# R2P_PS_module.net
KiCad netlist of a schematic drawn in EAGLE
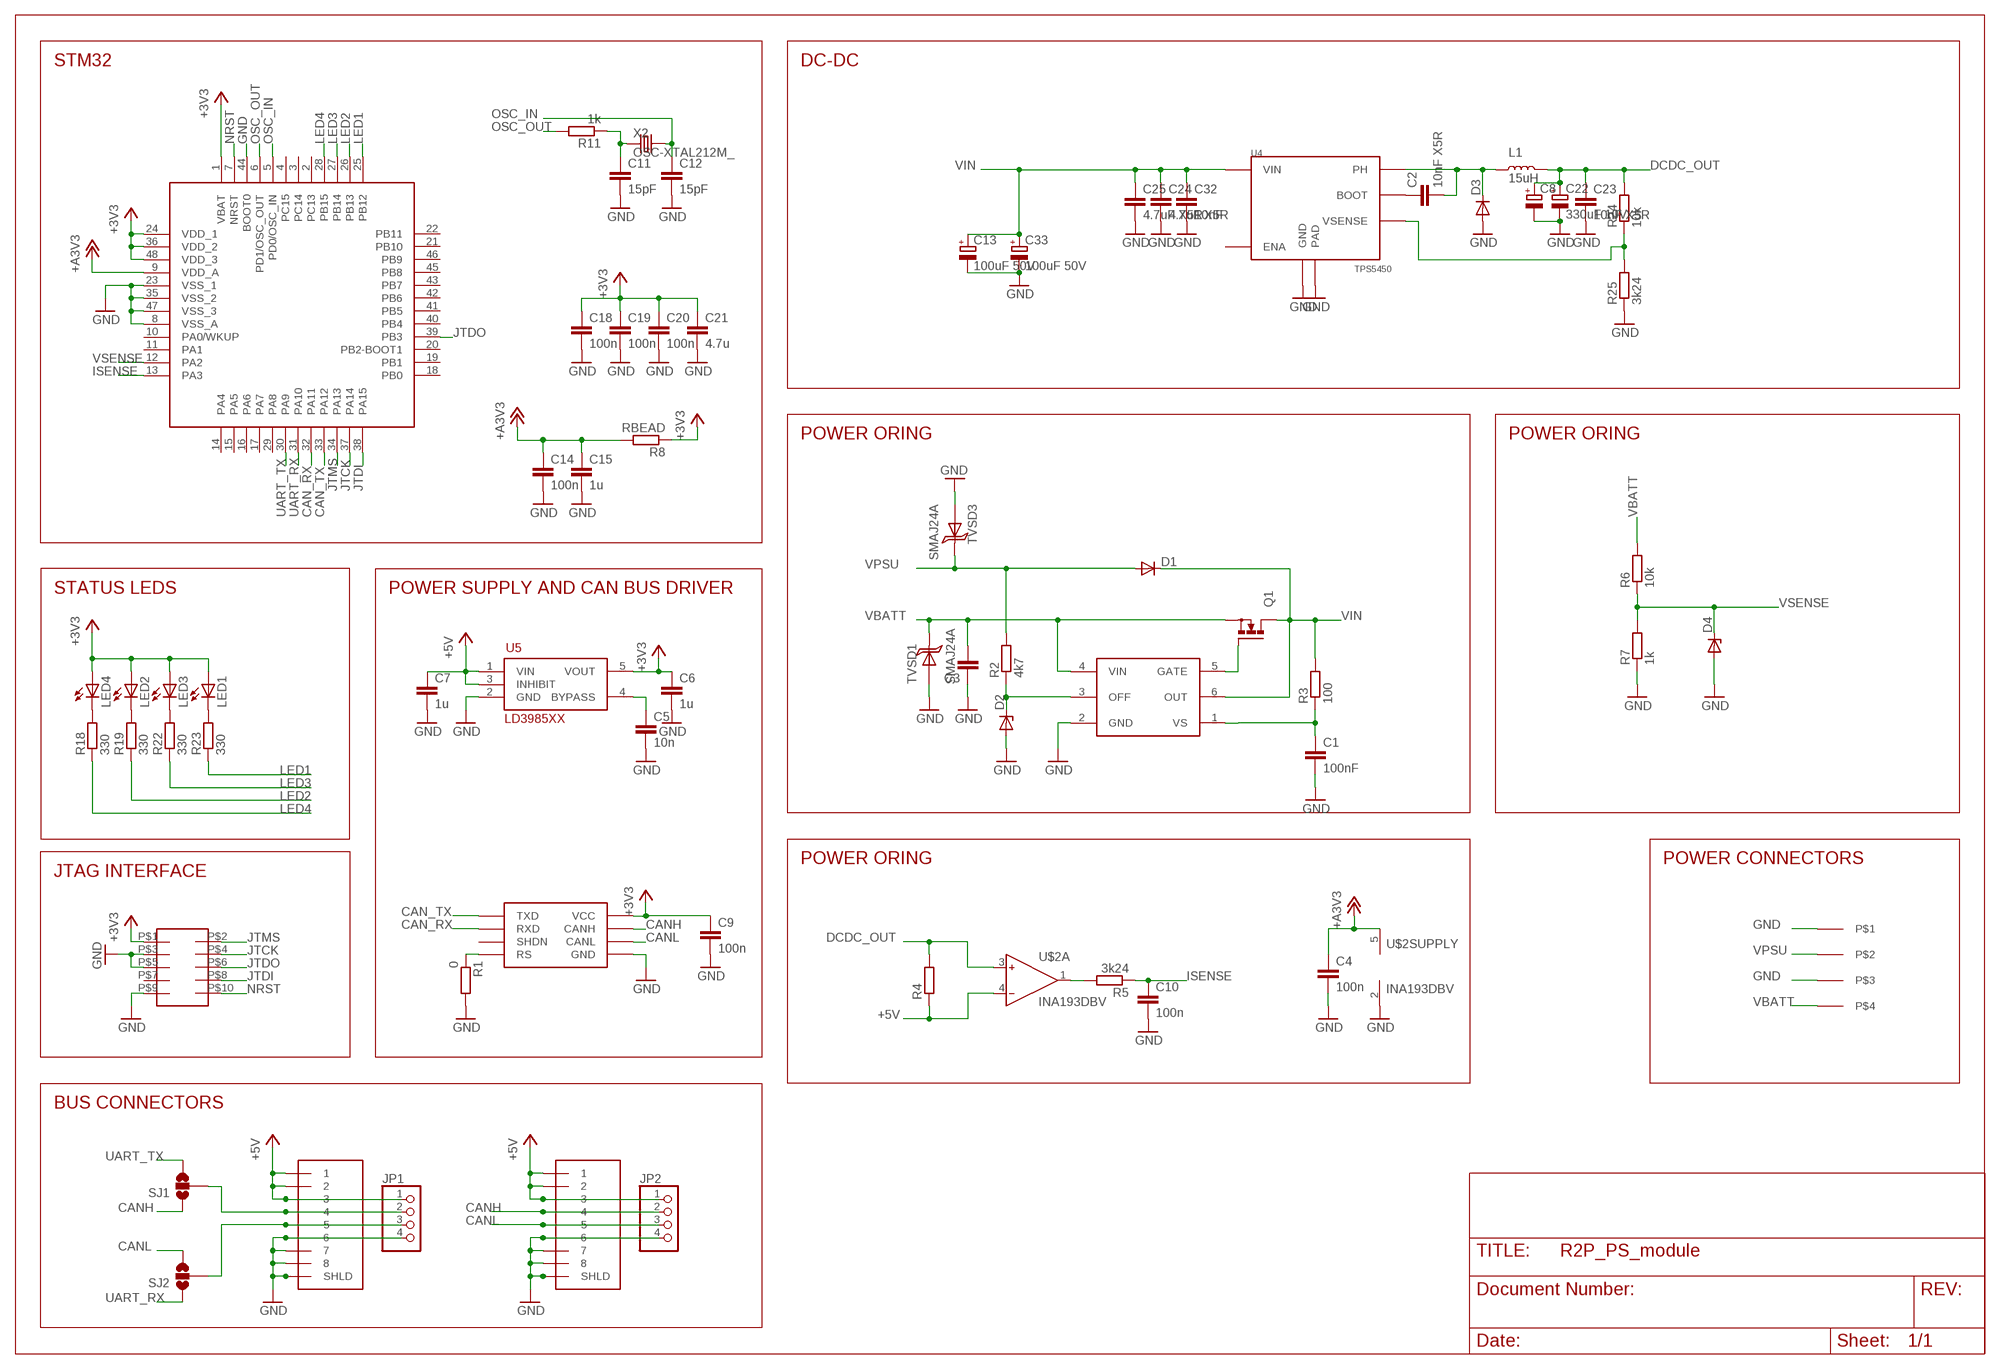
[diagram p0: schematic, sheet 1]

(export (version "E")
  (design (tool "Eeschema 10.0.6"))
  (components
    (comp (ref "1")
      (value "RJ45-43860")
      (footprint "eagle-import:0438600010")
      (libsource (lib "eagle-import") (part "RJ45-43860"))
    )
    (comp (ref "2")
      (value "RJ45-43860")
      (footprint "eagle-import:0438600010")
      (libsource (lib "eagle-import") (part "RJ45-43860"))
    )
    (comp (ref "C1")
      (value "100nF")
      (footprint "eagle-import:C0603")
      (libsource (lib "eagle-import") (part "C-EUC0603"))
    )
    (comp (ref "C2")
      (value "10nF X5R")
      (footprint "eagle-import:C0603")
      (libsource (lib "eagle-import") (part "C-EUC0603"))
    )
    (comp (ref "C3")
      (value "C-EUC0805")
      (footprint "eagle-import:C0805")
      (libsource (lib "eagle-import") (part "C-EUC0805"))
    )
    (comp (ref "C4")
      (value "100n")
      (footprint "eagle-import:C0603")
      (libsource (lib "eagle-import") (part "C-EUC0603"))
    )
    (comp (ref "C5")
      (value "10n")
      (footprint "eagle-import:C0603")
      (libsource (lib "eagle-import") (part "C-EUC0603"))
    )
    (comp (ref "C6")
      (value "1u")
      (footprint "eagle-import:C0603")
      (libsource (lib "eagle-import") (part "C-EUC0603"))
    )
    (comp (ref "C7")
      (value "1u")
      (footprint "eagle-import:C0603")
      (libsource (lib "eagle-import") (part "C-EUC0603"))
    )
    (comp (ref "C8")
      (value "CPOL-EUE5-10.5")
      (footprint "eagle-import:E5-10,5")
      (libsource (lib "eagle-import") (part "CPOL-EUE5-10.5"))
    )
    (comp (ref "C9")
      (value "100n")
      (footprint "eagle-import:C0603")
      (libsource (lib "eagle-import") (part "C-EUC0603"))
    )
    (comp (ref "C10")
      (value "100n")
      (footprint "eagle-import:C0603")
      (libsource (lib "eagle-import") (part "C-EUC0603"))
    )
    (comp (ref "C11")
      (value "15pF")
      (footprint "eagle-import:C0603")
      (libsource (lib "eagle-import") (part "C-EUC0603"))
    )
    (comp (ref "C12")
      (value "15pF")
      (footprint "eagle-import:C0603")
      (libsource (lib "eagle-import") (part "C-EUC0603"))
    )
    (comp (ref "C13")
      (value "100uF 50V")
      (footprint "eagle-import:E5-10,5")
      (libsource (lib "eagle-import") (part "CPOL-EUE5-10.5"))
    )
    (comp (ref "C14")
      (value "100n")
      (footprint "eagle-import:C0603")
      (libsource (lib "eagle-import") (part "C-EUC0603"))
    )
    (comp (ref "C15")
      (value "1u")
      (footprint "eagle-import:C0603")
      (libsource (lib "eagle-import") (part "C-EUC0603"))
    )
    (comp (ref "C18")
      (value "100n")
      (footprint "eagle-import:C0603")
      (libsource (lib "eagle-import") (part "C-EUC0603"))
    )
    (comp (ref "C19")
      (value "100n")
      (footprint "eagle-import:C0603")
      (libsource (lib "eagle-import") (part "C-EUC0603"))
    )
    (comp (ref "C20")
      (value "100n")
      (footprint "eagle-import:C0603")
      (libsource (lib "eagle-import") (part "C-EUC0603"))
    )
    (comp (ref "C21")
      (value "4.7u")
      (footprint "eagle-import:C0805")
      (libsource (lib "eagle-import") (part "C-EUC0805"))
    )
    (comp (ref "C22")
      (value "330uF 10V")
      (footprint "eagle-import:E2,5-7")
      (libsource (lib "eagle-import") (part "CPOL-EUE2.5-7"))
    )
    (comp (ref "C23")
      (value "10nF X5R")
      (footprint "eagle-import:C0603")
      (libsource (lib "eagle-import") (part "C-EUC0603"))
    )
    (comp (ref "C24")
      (value "4.7uF X5R")
      (footprint "eagle-import:C1210")
      (libsource (lib "eagle-import") (part "C-EUC1210"))
    )
    (comp (ref "C25")
      (value "4.7uF X5R")
      (footprint "eagle-import:C1210")
      (libsource (lib "eagle-import") (part "C-EUC1210"))
    )
    (comp (ref "C32")
      (value "10nF")
      (footprint "eagle-import:C0603")
      (libsource (lib "eagle-import") (part "C-EUC0603"))
    )
    (comp (ref "C33")
      (value "100uF 50V")
      (footprint "eagle-import:E2,5-7")
      (libsource (lib "eagle-import") (part "CPOL-EUE2.5-7"))
    )
    (comp (ref "D1")
      (value "DIODE-DO-214AC")
      (footprint "eagle-import:DO-214AC")
      (libsource (lib "eagle-import") (part "DIODE-DO-214AC"))
    )
    (comp (ref "D2")
      (value "ZENERSOD-323F")
      (footprint "eagle-import:SOD-323F")
      (libsource (lib "eagle-import") (part "ZENERSOD-323F"))
    )
    (comp (ref "D3")
      (value "DIODE-DO-214AC")
      (footprint "eagle-import:DO-214AC")
      (libsource (lib "eagle-import") (part "DIODE-DO-214AC"))
    )
    (comp (ref "D4")
      (value "ZENERSOD-323F")
      (footprint "eagle-import:SOD-323F")
      (libsource (lib "eagle-import") (part "ZENERSOD-323F"))
    )
    (comp (ref "JP1")
      (value "PINHD-1X4/90")
      (footprint "eagle-import:1X04_90")
      (libsource (lib "eagle-import") (part "PINHD-1X4/90"))
    )
    (comp (ref "JP2")
      (value "PINHD-1X4/90")
      (footprint "eagle-import:1X04_90")
      (libsource (lib "eagle-import") (part "PINHD-1X4/90"))
    )
    (comp (ref "L1")
      (value "15uH")
      (footprint "eagle-import:CDRH127")
      (libsource (lib "eagle-import") (part "CDRH127"))
    )
    (comp (ref "LED1")
      (value "LEDCHIPLED_0805")
      (footprint "eagle-import:CHIPLED_0805")
      (libsource (lib "eagle-import") (part "LEDCHIPLED_0805"))
    )
    (comp (ref "LED2")
      (value "LEDCHIPLED_0805")
      (footprint "eagle-import:CHIPLED_0805")
      (libsource (lib "eagle-import") (part "LEDCHIPLED_0805"))
    )
    (comp (ref "LED3")
      (value "LEDCHIPLED_0805")
      (footprint "eagle-import:CHIPLED_0805")
      (libsource (lib "eagle-import") (part "LEDCHIPLED_0805"))
    )
    (comp (ref "LED4")
      (value "LEDCHIPLED_0805")
      (footprint "eagle-import:CHIPLED_0805")
      (libsource (lib "eagle-import") (part "LEDCHIPLED_0805"))
    )
    (comp (ref "Q1")
      (value "N-MOSFET-SO8S")
      (footprint "eagle-import:SO-08")
      (libsource (lib "eagle-import") (part "N-MOSFET-SO8S"))
    )
    (comp (ref "R1")
      (value "0")
      (footprint "eagle-import:R0603")
      (libsource (lib "eagle-import") (part "R-EU_R0603"))
    )
    (comp (ref "R2")
      (value "4k7")
      (footprint "eagle-import:R0603")
      (libsource (lib "eagle-import") (part "R-EU_R0603"))
    )
    (comp (ref "R3")
      (value "100")
      (footprint "eagle-import:R0603")
      (libsource (lib "eagle-import") (part "R-EU_R0603"))
    )
    (comp (ref "R4")
      (value "R-EU_R2512")
      (footprint "eagle-import:R2512")
      (libsource (lib "eagle-import") (part "R-EU_R2512"))
    )
    (comp (ref "R5")
      (value "3k24")
      (footprint "eagle-import:R0603")
      (libsource (lib "eagle-import") (part "R-EU_R0603"))
    )
    (comp (ref "R6")
      (value "10k")
      (footprint "eagle-import:R0603")
      (libsource (lib "eagle-import") (part "R-EU_R0603"))
    )
    (comp (ref "R7")
      (value "1k")
      (footprint "eagle-import:R0603")
      (libsource (lib "eagle-import") (part "R-EU_R0603"))
    )
    (comp (ref "R8")
      (value "RBEAD")
      (footprint "eagle-import:R0603")
      (libsource (lib "eagle-import") (part "R-EU_R0603"))
    )
    (comp (ref "R11")
      (value "1k")
      (footprint "eagle-import:R0603")
      (libsource (lib "eagle-import") (part "R-EU_R0603"))
    )
    (comp (ref "R18")
      (value "330")
      (footprint "eagle-import:R0603")
      (libsource (lib "eagle-import") (part "R-EU_R0603"))
    )
    (comp (ref "R19")
      (value "330")
      (footprint "eagle-import:R0603")
      (libsource (lib "eagle-import") (part "R-EU_R0603"))
    )
    (comp (ref "R22")
      (value "330")
      (footprint "eagle-import:R0603")
      (libsource (lib "eagle-import") (part "R-EU_R0603"))
    )
    (comp (ref "R23")
      (value "330")
      (footprint "eagle-import:R0603")
      (libsource (lib "eagle-import") (part "R-EU_R0603"))
    )
    (comp (ref "R24")
      (value "10k")
      (footprint "eagle-import:R0603")
      (libsource (lib "eagle-import") (part "R-EU_R0603"))
    )
    (comp (ref "R25")
      (value "3k24")
      (footprint "eagle-import:R0603")
      (libsource (lib "eagle-import") (part "R-EU_R0603"))
    )
    (comp (ref "SJ1")
      (value "SOLDERJUMPER_2WAYPASTE1&2")
      (footprint "eagle-import:SJ_3_PASTE1&2")
      (libsource (lib "eagle-import") (part "SOLDERJUMPER_2WAYPASTE1&2"))
    )
    (comp (ref "SJ2")
      (value "SOLDERJUMPER_2WAYPASTE1&2")
      (footprint "eagle-import:SJ_3_PASTE1&2")
      (libsource (lib "eagle-import") (part "SOLDERJUMPER_2WAYPASTE1&2"))
    )
    (comp (ref "SOT1")
      (value "MAX3051")
      (footprint "eagle-import:SOT23-8L")
      (libsource (lib "eagle-import") (part "MAX3051"))
    )
    (comp (ref "TVSD1")
      (value "SMAJ24A")
      (footprint "eagle-import:SMA")
      (libsource (lib "eagle-import") (part "TVSDSMA"))
    )
    (comp (ref "TVSD3")
      (value "SMAJ24A")
      (footprint "eagle-import:SMA")
      (libsource (lib "eagle-import") (part "TVSDSMA"))
    )
    (comp (ref "U$1")
      (value "LM5050-1")
      (footprint "eagle-import:SOT23-6L")
      (libsource (lib "eagle-import") (part "LM5050-1"))
    )
    (comp (ref "U$2")
      (value "INA193DBV")
      (footprint "eagle-import:SOT23-5L")
      (libsource (lib "eagle-import") (part "INA193DBV"))
    )
    (comp (ref "U$3")
      (value "POWERCONN-4")
      (footprint "eagle-import:POWERCONN-4")
      (libsource (lib "eagle-import") (part "POWERCONN-4"))
    )
    (comp (ref "U$4")
      (value "FTSH-105")
      (footprint "eagle-import:FTSH-105")
      (libsource (lib "eagle-import") (part "FTSH-105"))
    )
    (comp (ref "U1")
      (value "STM32F103CX")
      (footprint "eagle-import:LQFP48")
      (libsource (lib "eagle-import") (part "STM32F103CX"))
    )
    (comp (ref "U4")
      (value "TPS5450")
      (footprint "eagle-import:POWERPAD-SO8")
      (libsource (lib "eagle-import") (part "TPS5450"))
    )
    (comp (ref "U5")
      (value "LD3985XX")
      (footprint "eagle-import:SOT23-5L")
      (libsource (lib "eagle-import") (part "LD3985XX"))
    )
    (comp (ref "X2")
      (value "OSC-XTAL212M_")
      (footprint "eagle-import:4X6")
      (libsource (lib "eagle-import") (part "OSC-XTAL212M_"))
    )
  )
  (nets
    (net (code "1") (name "+3V3") (class "Default")
      (node (ref "C18") (pin "1") (pinfunction "1_1") (pintype "passive"))
      (node (ref "C19") (pin "1") (pinfunction "1_1") (pintype "passive"))
      (node (ref "C20") (pin "1") (pinfunction "1_1") (pintype "passive"))
      (node (ref "C21") (pin "1") (pinfunction "1_1") (pintype "passive"))
      (node (ref "C6") (pin "1") (pinfunction "1_1") (pintype "passive"))
      (node (ref "C9") (pin "1") (pinfunction "1_1") (pintype "passive"))
      (node (ref "LED1") (pin "A") (pinfunction "A_A") (pintype "passive"))
      (node (ref "LED2") (pin "A") (pinfunction "A_A") (pintype "passive"))
      (node (ref "LED3") (pin "A") (pinfunction "A_A") (pintype "passive"))
      (node (ref "LED4") (pin "A") (pinfunction "A_A") (pintype "passive"))
      (node (ref "R8") (pin "1") (pinfunction "1_1") (pintype "passive"))
      (node (ref "SOT1") (pin "P$3") (pinfunction "VCC_P$3") (pintype "bidirectional"))
      (node (ref "U$4") (pin "P$1") (pinfunction "P$1_P$1") (pintype "bidirectional"))
      (node (ref "U1") (pin "1") (pinfunction "VBAT_1") (pintype "bidirectional"))
      (node (ref "U1") (pin "24") (pinfunction "VDD_1_24") (pintype "bidirectional"))
      (node (ref "U1") (pin "36") (pinfunction "VDD_2_36") (pintype "bidirectional"))
      (node (ref "U1") (pin "48") (pinfunction "VDD_3_48") (pintype "bidirectional"))
      (node (ref "U5") (pin "5") (pinfunction "VOUT_5") (pintype "bidirectional"))
    )
    (net (code "2") (name "+5V") (class "Default")
      (node (ref "1") (pin "P$1") (pinfunction "1_P$1") (pintype "bidirectional"))
      (node (ref "1") (pin "P$2") (pinfunction "2_P$2") (pintype "bidirectional"))
      (node (ref "1") (pin "P$3") (pinfunction "3_P$3") (pintype "bidirectional"))
      (node (ref "2") (pin "P$1") (pinfunction "1_P$1") (pintype "bidirectional"))
      (node (ref "2") (pin "P$2") (pinfunction "2_P$2") (pintype "bidirectional"))
      (node (ref "2") (pin "P$3") (pinfunction "3_P$3") (pintype "bidirectional"))
      (node (ref "C7") (pin "1") (pinfunction "1_1") (pintype "passive"))
      (node (ref "JP1") (pin "1") (pinfunction "1_1") (pintype "passive"))
      (node (ref "JP2") (pin "1") (pinfunction "1_1") (pintype "passive"))
      (node (ref "R4") (pin "1") (pinfunction "1_1") (pintype "passive"))
      (node (ref "U$2") (pin "4") (pinfunction "IN-_4") (pintype "input"))
      (node (ref "U5") (pin "1") (pinfunction "VIN_1") (pintype "bidirectional"))
      (node (ref "U5") (pin "3") (pinfunction "INHIBIT_3") (pintype "bidirectional"))
    )
    (net (code "3") (name "+A3V3") (class "Default")
      (node (ref "C14") (pin "1") (pinfunction "1_1") (pintype "passive"))
      (node (ref "C15") (pin "1") (pinfunction "1_1") (pintype "passive"))
      (node (ref "C4") (pin "1") (pinfunction "1_1") (pintype "passive"))
      (node (ref "R8") (pin "2") (pinfunction "2_2") (pintype "passive"))
      (node (ref "U$2") (pin "5") (pinfunction "V+_5") (pintype "power_in"))
      (node (ref "U1") (pin "9") (pinfunction "VDD_A_9") (pintype "bidirectional"))
    )
    (net (code "4") (name "/CANH") (class "Default")
      (node (ref "2") (pin "P$4") (pinfunction "4_P$4") (pintype "bidirectional"))
      (node (ref "JP2") (pin "2") (pinfunction "2_2") (pintype "passive"))
      (node (ref "SJ1") (pin "1") (pinfunction "1_1") (pintype "passive"))
      (node (ref "SOT1") (pin "P$7") (pinfunction "CANH_P$7") (pintype "bidirectional"))
    )
    (net (code "5") (name "/CANL") (class "Default")
      (node (ref "2") (pin "P$5") (pinfunction "5_P$5") (pintype "bidirectional"))
      (node (ref "JP2") (pin "3") (pinfunction "3_3") (pintype "passive"))
      (node (ref "SJ2") (pin "3") (pinfunction "3_3") (pintype "passive"))
      (node (ref "SOT1") (pin "P$6") (pinfunction "CANL_P$6") (pintype "bidirectional"))
    )
    (net (code "6") (name "/CAN_RX") (class "Default")
      (node (ref "SOT1") (pin "P$4") (pinfunction "RXD_P$4") (pintype "bidirectional"))
      (node (ref "U1") (pin "32") (pinfunction "PA11_32") (pintype "bidirectional"))
    )
    (net (code "7") (name "/CAN_TX") (class "Default")
      (node (ref "SOT1") (pin "P$1") (pinfunction "TXD_P$1") (pintype "bidirectional"))
      (node (ref "U1") (pin "33") (pinfunction "PA12_33") (pintype "bidirectional"))
    )
    (net (code "8") (name "/DCDC_OUT") (class "Default")
      (node (ref "C22") (pin "+") (pinfunction "+_+") (pintype "passive"))
      (node (ref "C23") (pin "1") (pinfunction "1_1") (pintype "passive"))
      (node (ref "C8") (pin "+") (pinfunction "+_+") (pintype "passive"))
      (node (ref "L1") (pin "P$2") (pinfunction "2_P$2") (pintype "passive"))
      (node (ref "R24") (pin "2") (pinfunction "2_2") (pintype "passive"))
      (node (ref "R4") (pin "2") (pinfunction "2_2") (pintype "passive"))
      (node (ref "U$2") (pin "3") (pinfunction "IN+_3") (pintype "input"))
    )
    (net (code "9") (name "/ISENSE") (class "Default")
      (node (ref "C10") (pin "1") (pinfunction "1_1") (pintype "passive"))
      (node (ref "R5") (pin "1") (pinfunction "1_1") (pintype "passive"))
      (node (ref "U1") (pin "13") (pinfunction "PA3_13") (pintype "bidirectional"))
    )
    (net (code "10") (name "/JTCK") (class "Default")
      (node (ref "U$4") (pin "P$4") (pinfunction "P$4_P$4") (pintype "bidirectional"))
      (node (ref "U1") (pin "37") (pinfunction "PA14_37") (pintype "bidirectional"))
    )
    (net (code "11") (name "/JTDI") (class "Default")
      (node (ref "U$4") (pin "P$8") (pinfunction "P$8_P$8") (pintype "bidirectional"))
      (node (ref "U1") (pin "38") (pinfunction "PA15_38") (pintype "bidirectional"))
    )
    (net (code "12") (name "/JTDO") (class "Default")
      (node (ref "U$4") (pin "P$6") (pinfunction "P$6_P$6") (pintype "bidirectional"))
      (node (ref "U1") (pin "39") (pinfunction "PB3_39") (pintype "bidirectional"))
    )
    (net (code "13") (name "/JTMS") (class "Default")
      (node (ref "U$4") (pin "P$2") (pinfunction "P$2_P$2") (pintype "bidirectional"))
      (node (ref "U1") (pin "34") (pinfunction "PA13_34") (pintype "bidirectional"))
    )
    (net (code "14") (name "/LED1") (class "Default")
      (node (ref "R23") (pin "1") (pinfunction "1_1") (pintype "passive"))
      (node (ref "U1") (pin "25") (pinfunction "PB12_25") (pintype "bidirectional"))
    )
    (net (code "15") (name "/LED2") (class "Default")
      (node (ref "R19") (pin "1") (pinfunction "1_1") (pintype "passive"))
      (node (ref "U1") (pin "26") (pinfunction "PB13_26") (pintype "bidirectional"))
    )
    (net (code "16") (name "/LED3") (class "Default")
      (node (ref "R22") (pin "1") (pinfunction "1_1") (pintype "passive"))
      (node (ref "U1") (pin "27") (pinfunction "PB14_27") (pintype "bidirectional"))
    )
    (net (code "17") (name "/LED4") (class "Default")
      (node (ref "R18") (pin "1") (pinfunction "1_1") (pintype "passive"))
      (node (ref "U1") (pin "28") (pinfunction "PB15_28") (pintype "bidirectional"))
    )
    (net (code "18") (name "/NRST") (class "Default")
      (node (ref "U$4") (pin "P$10") (pinfunction "P$10_P$10") (pintype "bidirectional"))
      (node (ref "U1") (pin "7") (pinfunction "NRST_7") (pintype "bidirectional"))
    )
    (net (code "19") (name "/OSC_IN") (class "Default")
      (node (ref "C12") (pin "1") (pinfunction "1_1") (pintype "passive"))
      (node (ref "U1") (pin "5") (pinfunction "PD0/OSC_IN_5") (pintype "bidirectional"))
      (node (ref "X2") (pin "2") (pinfunction "X2_2") (pintype "bidirectional"))
    )
    (net (code "20") (name "/OSC_OUT") (class "Default")
      (node (ref "R11") (pin "2") (pinfunction "2_2") (pintype "passive"))
      (node (ref "U1") (pin "6") (pinfunction "PD1/OSC_OUT_6") (pintype "bidirectional"))
    )
    (net (code "21") (name "/UART_RX") (class "Default")
      (node (ref "SJ2") (pin "1") (pinfunction "1_1") (pintype "passive"))
      (node (ref "U1") (pin "31") (pinfunction "PA10_31") (pintype "bidirectional"))
    )
    (net (code "22") (name "/UART_TX") (class "Default")
      (node (ref "SJ1") (pin "3") (pinfunction "3_3") (pintype "passive"))
      (node (ref "U1") (pin "30") (pinfunction "PA9_30") (pintype "bidirectional"))
    )
    (net (code "23") (name "/VBATT") (class "Default")
      (node (ref "C3") (pin "2") (pinfunction "2_2") (pintype "passive"))
      (node (ref "Q1") (pin "1") (pinfunction "S_1") (pintype "passive"))
      (node (ref "Q1") (pin "2") (pinfunction "S_2") (pintype "passive"))
      (node (ref "Q1") (pin "3") (pinfunction "S_3") (pintype "passive"))
      (node (ref "R6") (pin "2") (pinfunction "2_2") (pintype "passive"))
      (node (ref "TVSD1") (pin "C") (pinfunction "K_C") (pintype "bidirectional"))
      (node (ref "U$1") (pin "4") (pinfunction "VIN_4") (pintype "bidirectional"))
      (node (ref "U$3") (pin "P$4") (pinfunction "P$4_P$4") (pintype "bidirectional"))
    )
    (net (code "24") (name "/VIN") (class "Default")
      (node (ref "C13") (pin "+") (pinfunction "+_+") (pintype "passive"))
      (node (ref "C24") (pin "1") (pinfunction "1_1") (pintype "passive"))
      (node (ref "C25") (pin "1") (pinfunction "1_1") (pintype "passive"))
      (node (ref "C32") (pin "1") (pinfunction "1_1") (pintype "passive"))
      (node (ref "C33") (pin "+") (pinfunction "+_+") (pintype "passive"))
      (node (ref "D1") (pin "C") (pinfunction "C_C") (pintype "passive"))
      (node (ref "Q1") (pin "5") (pinfunction "D_5") (pintype "passive"))
      (node (ref "Q1") (pin "6") (pinfunction "D_6") (pintype "passive"))
      (node (ref "Q1") (pin "7") (pinfunction "D_7") (pintype "passive"))
      (node (ref "Q1") (pin "8") (pinfunction "D_8") (pintype "passive"))
      (node (ref "R3") (pin "2") (pinfunction "2_2") (pintype "passive"))
      (node (ref "U$1") (pin "6") (pinfunction "OUT_6") (pintype "bidirectional"))
      (node (ref "U4") (pin "P7") (pinfunction "VIN_P7") (pintype "bidirectional"))
    )
    (net (code "25") (name "/VPSU") (class "Default")
      (node (ref "D1") (pin "A") (pinfunction "A_A") (pintype "passive"))
      (node (ref "R2") (pin "2") (pinfunction "2_2") (pintype "passive"))
      (node (ref "TVSD3") (pin "C") (pinfunction "K_C") (pintype "bidirectional"))
      (node (ref "U$3") (pin "P$2") (pinfunction "P$2_P$2") (pintype "bidirectional"))
    )
    (net (code "26") (name "/VSENSE") (class "Default")
      (node (ref "D4") (pin "C") (pinfunction "C_C") (pintype "passive"))
      (node (ref "R6") (pin "1") (pinfunction "1_1") (pintype "passive"))
      (node (ref "R7") (pin "2") (pinfunction "2_2") (pintype "passive"))
      (node (ref "U1") (pin "12") (pinfunction "PA2_12") (pintype "bidirectional"))
    )
    (net (code "27") (name "GND") (class "Default")
      (node (ref "1") (pin "P$10") (pinfunction "P$1_P$10") (pintype "power_in"))
      (node (ref "1") (pin "P$6") (pinfunction "6_P$6") (pintype "bidirectional"))
      (node (ref "1") (pin "P$7") (pinfunction "7_P$7") (pintype "bidirectional"))
      (node (ref "1") (pin "P$8") (pinfunction "8_P$8") (pintype "bidirectional"))
      (node (ref "1") (pin "P$9") (pinfunction "SHLD_P$9") (pintype "power_in"))
      (node (ref "2") (pin "P$10") (pinfunction "P$1_P$10") (pintype "power_in"))
      (node (ref "2") (pin "P$6") (pinfunction "6_P$6") (pintype "bidirectional"))
      (node (ref "2") (pin "P$7") (pinfunction "7_P$7") (pintype "bidirectional"))
      (node (ref "2") (pin "P$8") (pinfunction "8_P$8") (pintype "bidirectional"))
      (node (ref "2") (pin "P$9") (pinfunction "SHLD_P$9") (pintype "power_in"))
      (node (ref "C1") (pin "2") (pinfunction "2_2") (pintype "passive"))
      (node (ref "C10") (pin "2") (pinfunction "2_2") (pintype "passive"))
      (node (ref "C11") (pin "2") (pinfunction "2_2") (pintype "passive"))
      (node (ref "C12") (pin "2") (pinfunction "2_2") (pintype "passive"))
      (node (ref "C13") (pin "-") (pinfunction "-_-") (pintype "passive"))
      (node (ref "C14") (pin "2") (pinfunction "2_2") (pintype "passive"))
      (node (ref "C15") (pin "2") (pinfunction "2_2") (pintype "passive"))
      (node (ref "C18") (pin "2") (pinfunction "2_2") (pintype "passive"))
      (node (ref "C19") (pin "2") (pinfunction "2_2") (pintype "passive"))
      (node (ref "C20") (pin "2") (pinfunction "2_2") (pintype "passive"))
      (node (ref "C21") (pin "2") (pinfunction "2_2") (pintype "passive"))
      (node (ref "C22") (pin "-") (pinfunction "-_-") (pintype "passive"))
      (node (ref "C23") (pin "2") (pinfunction "2_2") (pintype "passive"))
      (node (ref "C24") (pin "2") (pinfunction "2_2") (pintype "passive"))
      (node (ref "C25") (pin "2") (pinfunction "2_2") (pintype "passive"))
      (node (ref "C3") (pin "1") (pinfunction "1_1") (pintype "passive"))
      (node (ref "C32") (pin "2") (pinfunction "2_2") (pintype "passive"))
      (node (ref "C33") (pin "-") (pinfunction "-_-") (pintype "passive"))
      (node (ref "C4") (pin "2") (pinfunction "2_2") (pintype "passive"))
      (node (ref "C5") (pin "2") (pinfunction "2_2") (pintype "passive"))
      (node (ref "C6") (pin "2") (pinfunction "2_2") (pintype "passive"))
      (node (ref "C7") (pin "2") (pinfunction "2_2") (pintype "passive"))
      (node (ref "C8") (pin "-") (pinfunction "-_-") (pintype "passive"))
      (node (ref "C9") (pin "2") (pinfunction "2_2") (pintype "passive"))
      (node (ref "D2") (pin "A") (pinfunction "A_A") (pintype "passive"))
      (node (ref "D3") (pin "A") (pinfunction "A_A") (pintype "passive"))
      (node (ref "D4") (pin "A") (pinfunction "A_A") (pintype "passive"))
      (node (ref "JP1") (pin "4") (pinfunction "4_4") (pintype "passive"))
      (node (ref "JP2") (pin "4") (pinfunction "4_4") (pintype "passive"))
      (node (ref "R1") (pin "2") (pinfunction "2_2") (pintype "passive"))
      (node (ref "R25") (pin "1") (pinfunction "1_1") (pintype "passive"))
      (node (ref "R7") (pin "1") (pinfunction "1_1") (pintype "passive"))
      (node (ref "SOT1") (pin "P$2") (pinfunction "GND_P$2") (pintype "bidirectional"))
      (node (ref "TVSD1") (pin "A") (pinfunction "A_A") (pintype "bidirectional"))
      (node (ref "TVSD3") (pin "A") (pinfunction "A_A") (pintype "bidirectional"))
      (node (ref "U$1") (pin "2") (pinfunction "GND_2") (pintype "bidirectional"))
      (node (ref "U$2") (pin "2") (pinfunction "V-_2") (pintype "power_in"))
      (node (ref "U$3") (pin "P$1") (pinfunction "P$1_P$1") (pintype "bidirectional"))
      (node (ref "U$3") (pin "P$3") (pinfunction "P$3_P$3") (pintype "bidirectional"))
      (node (ref "U$4") (pin "P$3") (pinfunction "P$3_P$3") (pintype "bidirectional"))
      (node (ref "U$4") (pin "P$5") (pinfunction "P$5_P$5") (pintype "bidirectional"))
      (node (ref "U$4") (pin "P$9") (pinfunction "P$9_P$9") (pintype "bidirectional"))
      (node (ref "U1") (pin "23") (pinfunction "VSS_1_23") (pintype "bidirectional"))
      (node (ref "U1") (pin "35") (pinfunction "VSS_2_35") (pintype "bidirectional"))
      (node (ref "U1") (pin "44") (pinfunction "BOOT0_44") (pintype "bidirectional"))
      (node (ref "U1") (pin "47") (pinfunction "VSS_3_47") (pintype "bidirectional"))
      (node (ref "U1") (pin "8") (pinfunction "VSS_A_8") (pintype "bidirectional"))
      (node (ref "U4") (pin "P6") (pinfunction "GND_P6") (pintype "bidirectional"))
      (node (ref "U4") (pin "PAD") (pinfunction "PAD_PAD") (pintype "bidirectional"))
      (node (ref "U5") (pin "2") (pinfunction "GND_2") (pintype "bidirectional"))
    )
    (net (code "28") (name "Net-(1-4)") (class "Default")
      (node (ref "1") (pin "P$4") (pinfunction "4_P$4") (pintype "bidirectional"))
      (node (ref "JP1") (pin "2") (pinfunction "2_2") (pintype "passive"))
      (node (ref "SJ1") (pin "2") (pinfunction "2_2") (pintype "passive"))
    )
    (net (code "29") (name "Net-(1-5)") (class "Default")
      (node (ref "1") (pin "P$5") (pinfunction "5_P$5") (pintype "bidirectional"))
      (node (ref "JP1") (pin "3") (pinfunction "3_3") (pintype "passive"))
      (node (ref "SJ2") (pin "2") (pinfunction "2_2") (pintype "passive"))
    )
    (net (code "30") (name "Net-(L1-1)") (class "Default")
      (node (ref "C2") (pin "2") (pinfunction "2_2") (pintype "passive"))
      (node (ref "D3") (pin "C") (pinfunction "C_C") (pintype "passive"))
      (node (ref "L1") (pin "P$1") (pinfunction "1_P$1") (pintype "passive"))
      (node (ref "U4") (pin "P8") (pinfunction "PH_P8") (pintype "bidirectional"))
    )
    (net (code "31") (name "Net-(LED1-PadC)") (class "Default")
      (node (ref "LED1") (pin "C") (pinfunction "C_C") (pintype "passive"))
      (node (ref "R23") (pin "2") (pinfunction "2_2") (pintype "passive"))
    )
    (net (code "32") (name "Net-(LED2-PadC)") (class "Default")
      (node (ref "LED2") (pin "C") (pinfunction "C_C") (pintype "passive"))
      (node (ref "R19") (pin "2") (pinfunction "2_2") (pintype "passive"))
    )
    (net (code "33") (name "Net-(LED3-PadC)") (class "Default")
      (node (ref "LED3") (pin "C") (pinfunction "C_C") (pintype "passive"))
      (node (ref "R22") (pin "2") (pinfunction "2_2") (pintype "passive"))
    )
    (net (code "34") (name "Net-(LED4-PadC)") (class "Default")
      (node (ref "LED4") (pin "C") (pinfunction "C_C") (pintype "passive"))
      (node (ref "R18") (pin "2") (pinfunction "2_2") (pintype "passive"))
    )
    (net (code "35") (name "Net-(Q1-G)") (class "Default")
      (node (ref "Q1") (pin "4") (pinfunction "G_4") (pintype "passive"))
      (node (ref "U$1") (pin "5") (pinfunction "GATE_5") (pintype "bidirectional"))
    )
    (net (code "36") (name "Net-(SOT1-RS)") (class "Default")
      (node (ref "R1") (pin "1") (pinfunction "1_1") (pintype "passive"))
      (node (ref "SOT1") (pin "P$8") (pinfunction "RS_P$8") (pintype "bidirectional"))
    )
    (net (code "37") (name "Net-(U$1-OFF)") (class "Default")
      (node (ref "D2") (pin "C") (pinfunction "C_C") (pintype "passive"))
      (node (ref "R2") (pin "1") (pinfunction "1_1") (pintype "passive"))
      (node (ref "U$1") (pin "3") (pinfunction "OFF_3") (pintype "bidirectional"))
    )
    (net (code "38") (name "Net-(U$1-VS)") (class "Default")
      (node (ref "C1") (pin "1") (pinfunction "1_1") (pintype "passive"))
      (node (ref "R3") (pin "1") (pinfunction "1_1") (pintype "passive"))
      (node (ref "U$1") (pin "1") (pinfunction "VS_1") (pintype "bidirectional"))
    )
    (net (code "39") (name "Net-(U$2A-OUT)") (class "Default")
      (node (ref "R5") (pin "2") (pinfunction "2_2") (pintype "passive"))
      (node (ref "U$2") (pin "1") (pinfunction "OUT_1") (pintype "output"))
    )
    (net (code "40") (name "Net-(U4-BOOT)") (class "Default")
      (node (ref "C2") (pin "1") (pinfunction "1_1") (pintype "passive"))
      (node (ref "U4") (pin "P1") (pinfunction "BOOT_P1") (pintype "bidirectional"))
    )
    (net (code "41") (name "Net-(U4-VSENSE)") (class "Default")
      (node (ref "R24") (pin "1") (pinfunction "1_1") (pintype "passive"))
      (node (ref "R25") (pin "2") (pinfunction "2_2") (pintype "passive"))
      (node (ref "U4") (pin "P4") (pinfunction "VSENSE_P4") (pintype "bidirectional"))
    )
    (net (code "42") (name "Net-(U5-BYPASS)") (class "Default")
      (node (ref "C5") (pin "1") (pinfunction "1_1") (pintype "passive"))
      (node (ref "U5") (pin "4") (pinfunction "BYPASS_4") (pintype "bidirectional"))
    )
    (net (code "43") (name "Net-(X2-X1)") (class "Default")
      (node (ref "C11") (pin "1") (pinfunction "1_1") (pintype "passive"))
      (node (ref "R11") (pin "1") (pinfunction "1_1") (pintype "passive"))
      (node (ref "X2") (pin "1") (pinfunction "X1_1") (pintype "bidirectional"))
    )
    (net (code "44") (name "unconnected-(SOT1-SHDN-PadP$5)") (class "Default")
      (node (ref "SOT1") (pin "P$5") (pinfunction "SHDN_P$5") (pintype "bidirectional"))
    )
    (net (code "45") (name "unconnected-(U$4-PadP$7)") (class "Default")
      (node (ref "U$4") (pin "P$7") (pinfunction "P$7_P$7") (pintype "bidirectional"))
    )
    (net (code "46") (name "unconnected-(U1-PA0{slash}WKUP-Pad10)") (class "Default")
      (node (ref "U1") (pin "10") (pinfunction "PA0/WKUP_10") (pintype "bidirectional"))
    )
    (net (code "47") (name "unconnected-(U1-PA1-Pad11)") (class "Default")
      (node (ref "U1") (pin "11") (pinfunction "PA1_11") (pintype "bidirectional"))
    )
    (net (code "48") (name "unconnected-(U1-PA4-Pad14)") (class "Default")
      (node (ref "U1") (pin "14") (pinfunction "PA4_14") (pintype "bidirectional"))
    )
    (net (code "49") (name "unconnected-(U1-PA5-Pad15)") (class "Default")
      (node (ref "U1") (pin "15") (pinfunction "PA5_15") (pintype "bidirectional"))
    )
    (net (code "50") (name "unconnected-(U1-PA6-Pad16)") (class "Default")
      (node (ref "U1") (pin "16") (pinfunction "PA6_16") (pintype "bidirectional"))
    )
    (net (code "51") (name "unconnected-(U1-PA7-Pad17)") (class "Default")
      (node (ref "U1") (pin "17") (pinfunction "PA7_17") (pintype "bidirectional"))
    )
    (net (code "52") (name "unconnected-(U1-PA8-Pad29)") (class "Default")
      (node (ref "U1") (pin "29") (pinfunction "PA8_29") (pintype "bidirectional"))
    )
    (net (code "53") (name "unconnected-(U1-PB0-Pad18)") (class "Default")
      (node (ref "U1") (pin "18") (pinfunction "PB0_18") (pintype "bidirectional"))
    )
    (net (code "54") (name "unconnected-(U1-PB1-Pad19)") (class "Default")
      (node (ref "U1") (pin "19") (pinfunction "PB1_19") (pintype "bidirectional"))
    )
    (net (code "55") (name "unconnected-(U1-PB2-BOOT1-Pad20)") (class "Default")
      (node (ref "U1") (pin "20") (pinfunction "PB2-BOOT1_20") (pintype "bidirectional"))
    )
    (net (code "56") (name "unconnected-(U1-PB4-Pad40)") (class "Default")
      (node (ref "U1") (pin "40") (pinfunction "PB4_40") (pintype "bidirectional"))
    )
    (net (code "57") (name "unconnected-(U1-PB5-Pad41)") (class "Default")
      (node (ref "U1") (pin "41") (pinfunction "PB5_41") (pintype "bidirectional"))
    )
    (net (code "58") (name "unconnected-(U1-PB6-Pad42)") (class "Default")
      (node (ref "U1") (pin "42") (pinfunction "PB6_42") (pintype "bidirectional"))
    )
    (net (code "59") (name "unconnected-(U1-PB7-Pad43)") (class "Default")
      (node (ref "U1") (pin "43") (pinfunction "PB7_43") (pintype "bidirectional"))
    )
    (net (code "60") (name "unconnected-(U1-PB8-Pad45)") (class "Default")
      (node (ref "U1") (pin "45") (pinfunction "PB8_45") (pintype "bidirectional"))
    )
    (net (code "61") (name "unconnected-(U1-PB9-Pad46)") (class "Default")
      (node (ref "U1") (pin "46") (pinfunction "PB9_46") (pintype "bidirectional"))
    )
    (net (code "62") (name "unconnected-(U1-PB10-Pad21)") (class "Default")
      (node (ref "U1") (pin "21") (pinfunction "PB10_21") (pintype "bidirectional"))
    )
    (net (code "63") (name "unconnected-(U1-PB11-Pad22)") (class "Default")
      (node (ref "U1") (pin "22") (pinfunction "PB11_22") (pintype "bidirectional"))
    )
    (net (code "64") (name "unconnected-(U1-PC13-Pad2)") (class "Default")
      (node (ref "U1") (pin "2") (pinfunction "PC13_2") (pintype "bidirectional"))
    )
    (net (code "65") (name "unconnected-(U1-PC14-Pad3)") (class "Default")
      (node (ref "U1") (pin "3") (pinfunction "PC14_3") (pintype "bidirectional"))
    )
    (net (code "66") (name "unconnected-(U1-PC15-Pad4)") (class "Default")
      (node (ref "U1") (pin "4") (pinfunction "PC15_4") (pintype "bidirectional"))
    )
    (net (code "67") (name "unconnected-(U4-ENA-PadP5)") (class "Default")
      (node (ref "U4") (pin "P5") (pinfunction "ENA_P5") (pintype "bidirectional"))
    )
  )
)
